# PWM_Controller_Half_Bridge_ONLY_TL494.net
KiCad netlist of a schematic drawn in Altium Designer
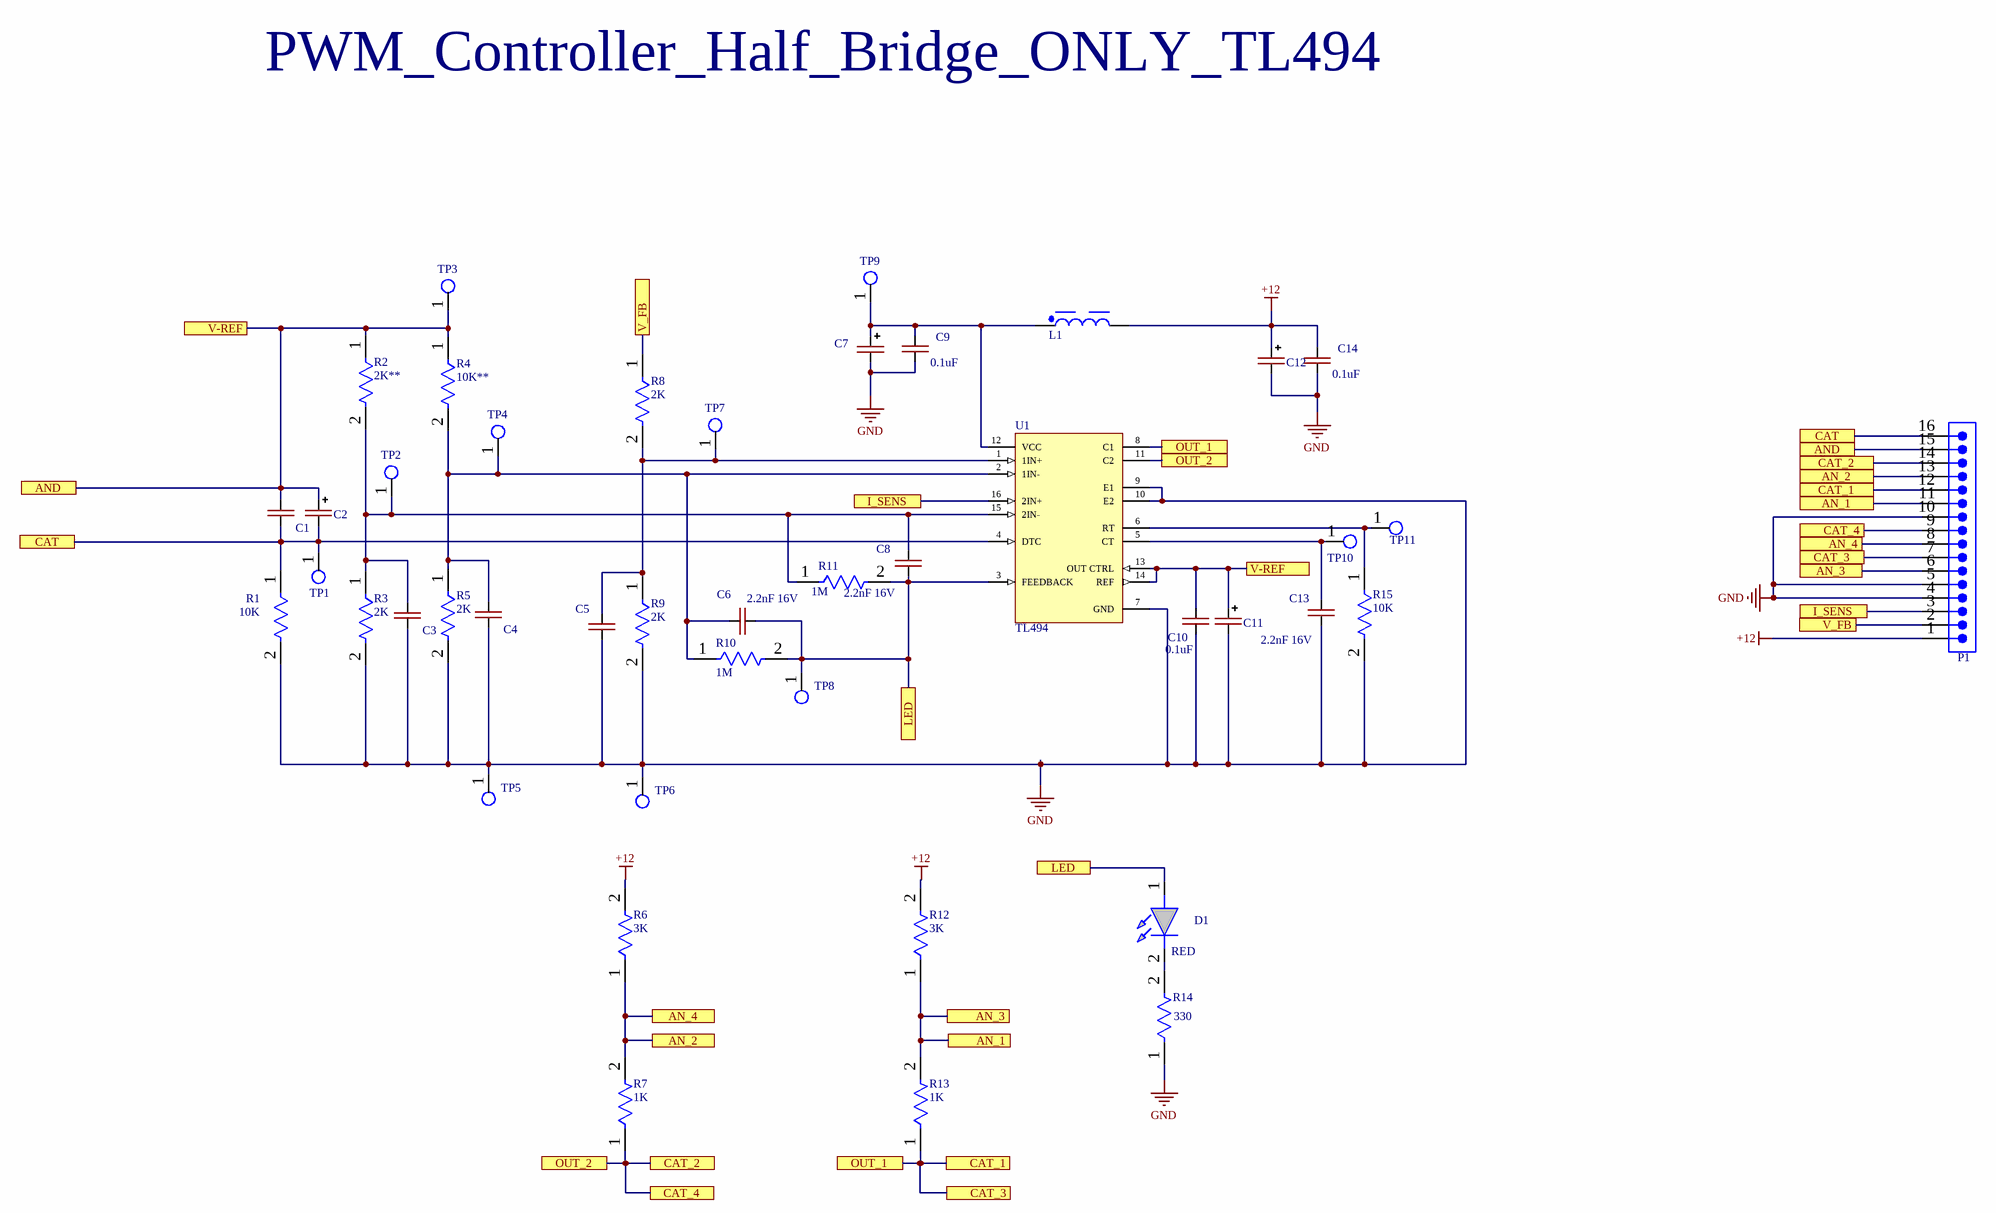
[diagram p0: PWM_Controller_Half_Bridge_ONLY_TL494.SchDoc]

(export (version "E")
  (design (tool "Eeschema 10.0.6"))
  (components
    (comp (ref "C1")
      (value "CAP-NON-POLAR")
      (footprint "CAP-0805")
      (libsource (lib "PASSIVE_COMPONENTS") (part "CAP-NON-POLAR"))
    )
    (comp (ref "C2")
      (value "CAP-POLAR")
      (footprint "CAP-TAN-D")
      (libsource (lib "PASSIVE_COMPONENTS") (part "CAP-POLAR"))
    )
    (comp (ref "C3")
      (value "CAP-NON-POLAR")
      (footprint "CAP-0805")
      (libsource (lib "PASSIVE_COMPONENTS") (part "CAP-NON-POLAR"))
    )
    (comp (ref "C4")
      (value "CAP-NON-POLAR")
      (footprint "CAP-0805")
      (libsource (lib "PASSIVE_COMPONENTS") (part "CAP-NON-POLAR"))
    )
    (comp (ref "C5")
      (value "CAP-NON-POLAR")
      (footprint "CAP-0805")
      (libsource (lib "PASSIVE_COMPONENTS") (part "CAP-NON-POLAR"))
    )
    (comp (ref "C6")
      (value "2.2nF 16V")
      (footprint "CAP-0805")
      (libsource (lib "PASSIVE_COMPONENTS") (part "CAP-NON-POLAR"))
    )
    (comp (ref "C7")
      (value "CAP-POLAR")
      (footprint "CAP_SMD_Size_E")
      (libsource (lib "PASSIVE_COMPONENTS") (part "CAP-POLAR"))
    )
    (comp (ref "C8")
      (value "2.2nF 16V")
      (footprint "CAP-0805")
      (libsource (lib "PASSIVE_COMPONENTS") (part "CAP-NON-POLAR"))
    )
    (comp (ref "C9")
      (value "0.1uF")
      (footprint "CAP-0805")
      (libsource (lib "PASSIVE_COMPONENTS") (part "CAP-NON-POLAR"))
    )
    (comp (ref "C10")
      (value "0.1uF")
      (footprint "CAP-0805")
      (libsource (lib "PASSIVE_COMPONENTS") (part "CAP-NON-POLAR"))
    )
    (comp (ref "C11")
      (value "CAP-POLAR")
      (footprint "CAP-TAN-D")
      (libsource (lib "PASSIVE_COMPONENTS") (part "CAP-POLAR"))
    )
    (comp (ref "C12")
      (value "CAP-POLAR")
      (footprint "CAP_SMD_Size_E")
      (libsource (lib "PASSIVE_COMPONENTS") (part "CAP-POLAR"))
    )
    (comp (ref "C13")
      (value "2.2nF 16V")
      (footprint "CAP-0805")
      (libsource (lib "PASSIVE_COMPONENTS") (part "CAP-NON-POLAR"))
    )
    (comp (ref "C14")
      (value "0.1uF")
      (footprint "CAP-0805")
      (libsource (lib "PASSIVE_COMPONENTS") (part "CAP-NON-POLAR"))
    )
    (comp (ref "D1")
      (value "RED")
      (footprint "LED_RED")
      (description "WURTH ELEKTRONIK - 151031YS06000 - LED, Yellow, Through Hole, T-1 (3mm), 30 mA, 2 V, 590 nm")
      (fields
        (field (name "MANUFACTURER_PART_NUMBER") "151031YS06000")
        (field (name "MOUSER PART NUMBER") "710-151031YS06000")
      )
      (libsource (lib "Optic-LED") (part "LED"))
    )
    (comp (ref "L1")
      (value "47µH, 1.17A")
      (footprint "WE-PD2_7850")
      (description "WE-PD2 SMT Power Inductor, size 7850, 47µH, 1.17A, 0.18Ω")
      (fields
        (field (name "MANUFACTURER PART NUMBER") "744775147")
        (field (name "MANUFACTURER") "Wurth Elektronik")
      )
      (libsource (lib "WE-PD2 (rev22d)") (part "744775147"))
    )
    (comp (ref "P1")
      (value "61301611021")
      (footprint "61301611021")
      (description "WR-PHD Pin Header, THT, Angled, pitch 2.54mm, 1 Row, 16P")
      (fields (field (name "MANUFACTURER") "Wurth Elektronik"))
      (libsource (lib "Altium_WR-PHD (rev22b)") (part "61301611021"))
    )
    (comp (ref "R1")
      (value "10K")
      (footprint "RES-0805")
      (libsource (lib "PASSIVE_COMPONENTS") (part "RES-CONST"))
    )
    (comp (ref "R2")
      (value "2K**")
      (footprint "RES-0805")
      (description "2K")
      (libsource (lib "PASSIVE_COMPONENTS") (part "RES-CONST"))
    )
    (comp (ref "R3")
      (value "2K")
      (footprint "RES-0805")
      (libsource (lib "PASSIVE_COMPONENTS") (part "RES-CONST"))
    )
    (comp (ref "R4")
      (value "10K**")
      (footprint "RES-0805")
      (description "10K")
      (libsource (lib "PASSIVE_COMPONENTS") (part "RES-CONST"))
    )
    (comp (ref "R5")
      (value "2K")
      (footprint "RES-0805")
      (libsource (lib "PASSIVE_COMPONENTS") (part "RES-CONST"))
    )
    (comp (ref "R6")
      (value "3K")
      (footprint "RES-0805")
      (libsource (lib "PASSIVE_COMPONENTS") (part "RES-CONST"))
    )
    (comp (ref "R7")
      (value "1K")
      (footprint "RES-0805")
      (libsource (lib "PASSIVE_COMPONENTS") (part "RES-CONST"))
    )
    (comp (ref "R8")
      (value "2K")
      (footprint "RES-0805")
      (libsource (lib "PASSIVE_COMPONENTS") (part "RES-CONST"))
    )
    (comp (ref "R9")
      (value "2K")
      (footprint "RES-0805")
      (libsource (lib "PASSIVE_COMPONENTS") (part "RES-CONST"))
    )
    (comp (ref "R10")
      (value "1M")
      (footprint "RES-0805")
      (libsource (lib "PASSIVE_COMPONENTS") (part "RES-CONST"))
    )
    (comp (ref "R11")
      (value "1M")
      (footprint "RES-0805")
      (libsource (lib "PASSIVE_COMPONENTS") (part "RES-CONST"))
    )
    (comp (ref "R12")
      (value "3K")
      (footprint "RES-0805")
      (libsource (lib "PASSIVE_COMPONENTS") (part "RES-CONST"))
    )
    (comp (ref "R13")
      (value "1K")
      (footprint "RES-0805")
      (libsource (lib "PASSIVE_COMPONENTS") (part "RES-CONST"))
    )
    (comp (ref "R14")
      (value "330")
      (footprint "RES-0805")
      (libsource (lib "PASSIVE_COMPONENTS") (part "RES-CONST"))
    )
    (comp (ref "R15")
      (value "10K")
      (footprint "RES-0805")
      (libsource (lib "PASSIVE_COMPONENTS") (part "RES-CONST"))
    )
    (comp (ref "TP1")
      (value "~")
      (footprint "Test_Point")
      (description "Test_Point")
      (libsource (lib "Connectors") (part "TP_PCB?"))
    )
    (comp (ref "TP2")
      (value "~")
      (footprint "Test_Point")
      (description "Test_Point")
      (libsource (lib "Connectors") (part "TP_PCB?"))
    )
    (comp (ref "TP3")
      (value "~")
      (footprint "Test_Point")
      (description "Test_Point")
      (libsource (lib "Connectors") (part "TP_PCB?"))
    )
    (comp (ref "TP4")
      (value "~")
      (footprint "Test_Point")
      (description "Test_Point")
      (libsource (lib "Connectors") (part "TP_PCB?"))
    )
    (comp (ref "TP5")
      (value "~")
      (footprint "Test_Point")
      (description "Test_Point")
      (libsource (lib "Connectors") (part "TP_PCB?"))
    )
    (comp (ref "TP6")
      (value "~")
      (footprint "Test_Point")
      (description "Test_Point")
      (libsource (lib "Connectors") (part "TP_PCB?"))
    )
    (comp (ref "TP7")
      (value "~")
      (footprint "Test_Point")
      (description "Test_Point")
      (libsource (lib "Connectors") (part "TP_PCB?"))
    )
    (comp (ref "TP8")
      (value "~")
      (footprint "Test_Point")
      (description "Test_Point")
      (libsource (lib "Connectors") (part "TP_PCB?"))
    )
    (comp (ref "TP9")
      (value "~")
      (footprint "Test_Point")
      (description "Test_Point")
      (libsource (lib "Connectors") (part "TP_PCB?"))
    )
    (comp (ref "TP10")
      (value "~")
      (footprint "Test_Point")
      (description "Test_Point")
      (libsource (lib "Connectors") (part "TP_PCB?"))
    )
    (comp (ref "TP11")
      (value "~")
      (footprint "Test_Point")
      (description "Test_Point")
      (libsource (lib "Connectors") (part "TP_PCB?"))
    )
    (comp (ref "U1")
      (value "TL494")
      (footprint "SOIC-16-M")
      (description "TL494 Pwm controller")
      (libsource (lib "Integrated_Circuts") (part "TL494"))
    )
  )
  (nets
    (net (code "1") (name "+12") (class "Default")
      (node (ref "C12") (pin "1") (pinfunction "+_1") (pintype "passive"))
      (node (ref "C14") (pin "2") (pinfunction "2_2") (pintype "passive"))
      (node (ref "L1") (pin "2") (pinfunction "2_2") (pintype "passive"))
      (node (ref "P1") (pin "1") (pinfunction "1_1") (pintype "passive"))
      (node (ref "R12") (pin "2") (pinfunction "2_2") (pintype "passive"))
      (node (ref "R6") (pin "2") (pinfunction "2_2") (pintype "passive"))
    )
    (net (code "2") (name "/AND") (class "Default")
      (node (ref "C1") (pin "2") (pinfunction "2_2") (pintype "passive"))
      (node (ref "C10") (pin "2") (pinfunction "2_2") (pintype "passive"))
      (node (ref "C11") (pin "1") (pinfunction "+_1") (pintype "passive"))
      (node (ref "C2") (pin "1") (pinfunction "+_1") (pintype "passive"))
      (node (ref "P1") (pin "15") (pinfunction "15_15") (pintype "passive"))
      (node (ref "R2") (pin "1") (pinfunction "1_1") (pintype "passive"))
      (node (ref "R4") (pin "1") (pinfunction "1_1") (pintype "passive"))
      (node (ref "TP3") (pin "1") (pinfunction "G9_1") (pintype "passive"))
      (node (ref "U1") (pin "13") (pinfunction "OUT_CTRL_13") (pintype "input"))
      (node (ref "U1") (pin "14") (pinfunction "REF_14") (pintype "output"))
    )
    (net (code "3") (name "/AN_1") (class "Default")
      (node (ref "P1") (pin "11") (pinfunction "11_11") (pintype "passive"))
      (node (ref "P1") (pin "6") (pinfunction "6_6") (pintype "passive"))
      (node (ref "R12") (pin "1") (pinfunction "1_1") (pintype "passive"))
      (node (ref "R13") (pin "2") (pinfunction "2_2") (pintype "passive"))
    )
    (net (code "4") (name "/AN_2") (class "Default")
      (node (ref "P1") (pin "13") (pinfunction "13_13") (pintype "passive"))
      (node (ref "P1") (pin "8") (pinfunction "8_8") (pintype "passive"))
      (node (ref "R6") (pin "1") (pinfunction "1_1") (pintype "passive"))
      (node (ref "R7") (pin "2") (pinfunction "2_2") (pintype "passive"))
    )
    (net (code "5") (name "/CAT") (class "Default")
      (node (ref "C1") (pin "1") (pinfunction "1_1") (pintype "passive"))
      (node (ref "C2") (pin "2") (pinfunction "-_2") (pintype "passive"))
      (node (ref "P1") (pin "16") (pinfunction "16_16") (pintype "passive"))
      (node (ref "R1") (pin "1") (pinfunction "1_1") (pintype "passive"))
      (node (ref "TP1") (pin "1") (pinfunction "G9_1") (pintype "passive"))
      (node (ref "U1") (pin "4") (pinfunction "DTC_4") (pintype "input"))
    )
    (net (code "6") (name "/CAT_1") (class "Default")
      (node (ref "P1") (pin "12") (pinfunction "12_12") (pintype "passive"))
      (node (ref "P1") (pin "7") (pinfunction "7_7") (pintype "passive"))
      (node (ref "R13") (pin "1") (pinfunction "1_1") (pintype "passive"))
      (node (ref "U1") (pin "8") (pinfunction "C1_8") (pintype "passive"))
    )
    (net (code "7") (name "/CAT_2") (class "Default")
      (node (ref "P1") (pin "14") (pinfunction "14_14") (pintype "passive"))
      (node (ref "P1") (pin "9") (pinfunction "9_9") (pintype "passive"))
      (node (ref "R7") (pin "1") (pinfunction "1_1") (pintype "passive"))
      (node (ref "U1") (pin "11") (pinfunction "C2_11") (pintype "passive"))
    )
    (net (code "8") (name "/I_SENS") (class "Default")
      (node (ref "P1") (pin "3") (pinfunction "3_3") (pintype "passive"))
      (node (ref "U1") (pin "16") (pinfunction "2IN+_16") (pintype "input"))
    )
    (net (code "9") (name "/LED") (class "Default")
      (node (ref "C6") (pin "1") (pinfunction "1_1") (pintype "passive"))
      (node (ref "C8") (pin "1") (pinfunction "1_1") (pintype "passive"))
      (node (ref "D1") (pin "1") (pinfunction "A_1") (pintype "passive"))
      (node (ref "R10") (pin "2") (pinfunction "2_2") (pintype "passive"))
      (node (ref "R11") (pin "2") (pinfunction "2_2") (pintype "passive"))
      (node (ref "TP8") (pin "1") (pinfunction "G9_1") (pintype "passive"))
      (node (ref "U1") (pin "3") (pinfunction "FEEDBACK_3") (pintype "input"))
    )
    (net (code "10") (name "/V_FB") (class "Default")
      (node (ref "P1") (pin "2") (pinfunction "2_2") (pintype "passive"))
      (node (ref "R8") (pin "1") (pinfunction "1_1") (pintype "passive"))
    )
    (net (code "11") (name "GND") (class "Default")
      (node (ref "C10") (pin "1") (pinfunction "1_1") (pintype "passive"))
      (node (ref "C11") (pin "2") (pinfunction "-_2") (pintype "passive"))
      (node (ref "C12") (pin "2") (pinfunction "-_2") (pintype "passive"))
      (node (ref "C13") (pin "1") (pinfunction "1_1") (pintype "passive"))
      (node (ref "C14") (pin "1") (pinfunction "1_1") (pintype "passive"))
      (node (ref "C3") (pin "1") (pinfunction "1_1") (pintype "passive"))
      (node (ref "C4") (pin "1") (pinfunction "1_1") (pintype "passive"))
      (node (ref "C5") (pin "1") (pinfunction "1_1") (pintype "passive"))
      (node (ref "C7") (pin "2") (pinfunction "-_2") (pintype "passive"))
      (node (ref "C9") (pin "1") (pinfunction "1_1") (pintype "passive"))
      (node (ref "P1") (pin "10") (pinfunction "10_10") (pintype "passive"))
      (node (ref "P1") (pin "4") (pinfunction "4_4") (pintype "passive"))
      (node (ref "P1") (pin "5") (pinfunction "5_5") (pintype "passive"))
      (node (ref "R1") (pin "2") (pinfunction "2_2") (pintype "passive"))
      (node (ref "R14") (pin "1") (pinfunction "1_1") (pintype "passive"))
      (node (ref "R15") (pin "2") (pinfunction "2_2") (pintype "passive"))
      (node (ref "R3") (pin "2") (pinfunction "2_2") (pintype "passive"))
      (node (ref "R5") (pin "2") (pinfunction "2_2") (pintype "passive"))
      (node (ref "R9") (pin "2") (pinfunction "2_2") (pintype "passive"))
      (node (ref "TP5") (pin "1") (pinfunction "G9_1") (pintype "passive"))
      (node (ref "TP6") (pin "1") (pinfunction "G9_1") (pintype "passive"))
      (node (ref "U1") (pin "10") (pinfunction "E2_10") (pintype "passive"))
      (node (ref "U1") (pin "7") (pinfunction "GND_7") (pintype "power_in"))
      (node (ref "U1") (pin "9") (pinfunction "E1_9") (pintype "passive"))
    )
    (net (code "12") (name "Net-(C7-+)") (class "Default")
      (node (ref "C7") (pin "1") (pinfunction "+_1") (pintype "passive"))
      (node (ref "C9") (pin "2") (pinfunction "2_2") (pintype "passive"))
      (node (ref "L1") (pin "1") (pinfunction "1_1") (pintype "passive"))
      (node (ref "TP9") (pin "1") (pinfunction "G9_1") (pintype "passive"))
      (node (ref "U1") (pin "12") (pinfunction "VCC_12") (pintype "power_in"))
    )
    (net (code "13") (name "Net-(D1-K)") (class "Default")
      (node (ref "D1") (pin "2") (pinfunction "K_2") (pintype "passive"))
      (node (ref "R14") (pin "2") (pinfunction "2_2") (pintype "passive"))
    )
    (net (code "14") (name "Net-(TP2-G9)") (class "Default")
      (node (ref "C3") (pin "2") (pinfunction "2_2") (pintype "passive"))
      (node (ref "C8") (pin "2") (pinfunction "2_2") (pintype "passive"))
      (node (ref "R11") (pin "1") (pinfunction "1_1") (pintype "passive"))
      (node (ref "R2") (pin "2") (pinfunction "2_2") (pintype "passive"))
      (node (ref "R3") (pin "1") (pinfunction "1_1") (pintype "passive"))
      (node (ref "TP2") (pin "1") (pinfunction "G9_1") (pintype "passive"))
      (node (ref "U1") (pin "15") (pinfunction "2IN-_15") (pintype "input"))
    )
    (net (code "15") (name "Net-(TP4-G9)") (class "Default")
      (node (ref "C4") (pin "2") (pinfunction "2_2") (pintype "passive"))
      (node (ref "C6") (pin "2") (pinfunction "2_2") (pintype "passive"))
      (node (ref "R10") (pin "1") (pinfunction "1_1") (pintype "passive"))
      (node (ref "R4") (pin "2") (pinfunction "2_2") (pintype "passive"))
      (node (ref "R5") (pin "1") (pinfunction "1_1") (pintype "passive"))
      (node (ref "TP4") (pin "1") (pinfunction "G9_1") (pintype "passive"))
      (node (ref "U1") (pin "2") (pinfunction "1IN-_2") (pintype "input"))
    )
    (net (code "16") (name "Net-(TP7-G9)") (class "Default")
      (node (ref "C5") (pin "2") (pinfunction "2_2") (pintype "passive"))
      (node (ref "R8") (pin "2") (pinfunction "2_2") (pintype "passive"))
      (node (ref "R9") (pin "1") (pinfunction "1_1") (pintype "passive"))
      (node (ref "TP7") (pin "1") (pinfunction "G9_1") (pintype "passive"))
      (node (ref "U1") (pin "1") (pinfunction "1IN+_1") (pintype "input"))
    )
    (net (code "17") (name "Net-(TP10-G9)") (class "Default")
      (node (ref "C13") (pin "2") (pinfunction "2_2") (pintype "passive"))
      (node (ref "TP10") (pin "1") (pinfunction "G9_1") (pintype "passive"))
      (node (ref "U1") (pin "5") (pinfunction "CT_5") (pintype "passive"))
    )
    (net (code "18") (name "Net-(TP11-G9)") (class "Default")
      (node (ref "R15") (pin "1") (pinfunction "1_1") (pintype "passive"))
      (node (ref "TP11") (pin "1") (pinfunction "G9_1") (pintype "passive"))
      (node (ref "U1") (pin "6") (pinfunction "RT_6") (pintype "passive"))
    )
  )
)
